# DisolvedOxygen.net
KiCad netlist of a schematic drawn in EAGLE
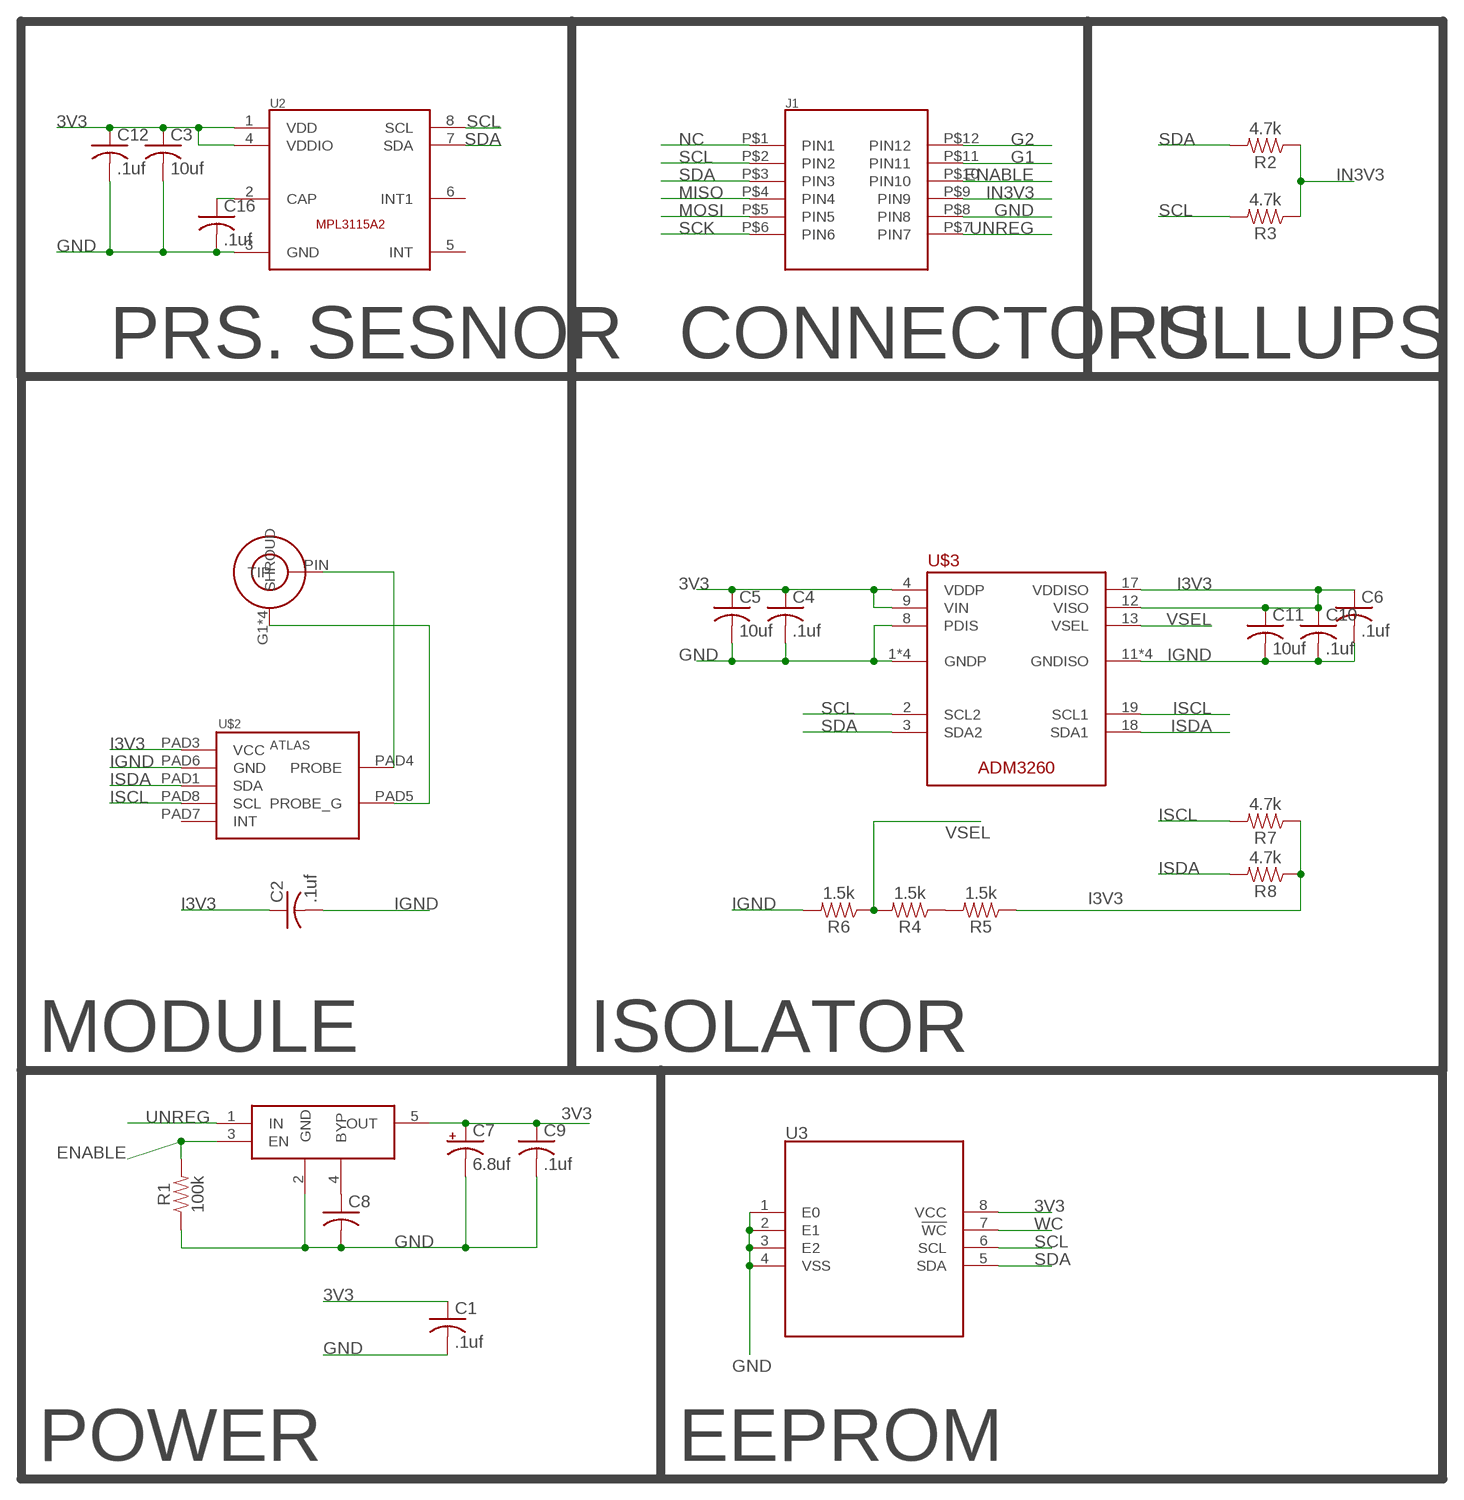
[diagram p0: schematic, sheet 1]

(export (version "E")
  (design (tool "Eeschema 10.0.6"))
  (components
    (comp (ref "C1")
      (value ".1uf")
      (footprint "eagle-import:C0603K")
      (libsource (lib "eagle-import") (part "C-USC0603K"))
    )
    (comp (ref "C2")
      (value ".1uf")
      (footprint "eagle-import:C0603K")
      (libsource (lib "eagle-import") (part "C-USC0603K"))
    )
    (comp (ref "C3")
      (value "10uf")
      (footprint "eagle-import:C0603K")
      (libsource (lib "eagle-import") (part "C-USC0603K"))
    )
    (comp (ref "C4")
      (value ".1uf")
      (footprint "eagle-import:C0603K")
      (libsource (lib "eagle-import") (part "C-USC0603K"))
    )
    (comp (ref "C5")
      (value "10uf")
      (footprint "eagle-import:C0603K")
      (libsource (lib "eagle-import") (part "C-USC0603K"))
    )
    (comp (ref "C6")
      (value ".1uf")
      (footprint "eagle-import:C0603K")
      (libsource (lib "eagle-import") (part "C-USC0603K"))
    )
    (comp (ref "C7")
      (value "6.8uf")
      (footprint "eagle-import:A_3216-18R")
      (libsource (lib "eagle-import") (part "CPOL-USA/3216-18R"))
    )
    (comp (ref "C8")
      (value "C-USC0603K")
      (footprint "eagle-import:C0603K")
      (libsource (lib "eagle-import") (part "C-USC0603K"))
    )
    (comp (ref "C9")
      (value ".1uf")
      (footprint "eagle-import:C0603K")
      (libsource (lib "eagle-import") (part "C-USC0603K"))
    )
    (comp (ref "C10")
      (value ".1uf")
      (footprint "eagle-import:C0603K")
      (libsource (lib "eagle-import") (part "C-USC0603K"))
    )
    (comp (ref "C11")
      (value "10uf")
      (footprint "eagle-import:C0603K")
      (libsource (lib "eagle-import") (part "C-USC0603K"))
    )
    (comp (ref "C12")
      (value ".1uf")
      (footprint "eagle-import:C0603K")
      (libsource (lib "eagle-import") (part "C-USC0603K"))
    )
    (comp (ref "C16")
      (value ".1uf")
      (footprint "eagle-import:C0603K")
      (libsource (lib "eagle-import") (part "C-USC0603K"))
    )
    (comp (ref "J1")
      (value "2X6-HEADERS")
      (footprint "eagle-import:M20-7810645")
      (libsource (lib "eagle-import") (part "2X6-HEADERS"))
    )
    (comp (ref "R1")
      (value "100k")
      (footprint "eagle-import:0603")
      (libsource (lib "eagle-import") (part "100KOHM-0603-1/10W-1%"))
    )
    (comp (ref "R2")
      (value "4.7k")
      (footprint "eagle-import:0603")
      (libsource (lib "eagle-import") (part "100KOHM-0603-1/10W-1%"))
    )
    (comp (ref "R3")
      (value "4.7k")
      (footprint "eagle-import:0603")
      (libsource (lib "eagle-import") (part "100KOHM-0603-1/10W-1%"))
    )
    (comp (ref "R4")
      (value "1.5k")
      (footprint "eagle-import:0603")
      (libsource (lib "eagle-import") (part "100KOHM-0603-1/10W-1%"))
    )
    (comp (ref "R5")
      (value "1.5k")
      (footprint "eagle-import:0603")
      (libsource (lib "eagle-import") (part "100KOHM-0603-1/10W-1%"))
    )
    (comp (ref "R6")
      (value "1.5k")
      (footprint "eagle-import:0603")
      (libsource (lib "eagle-import") (part "100KOHM-0603-1/10W-1%"))
    )
    (comp (ref "R7")
      (value "4.7k")
      (footprint "eagle-import:0603")
      (libsource (lib "eagle-import") (part "100KOHM-0603-1/10W-1%"))
    )
    (comp (ref "R8")
      (value "4.7k")
      (footprint "eagle-import:0603")
      (libsource (lib "eagle-import") (part "100KOHM-0603-1/10W-1%"))
    )
    (comp (ref "U$1")
      (value "5-1814832-1")
      (footprint "eagle-import:5-1814832-1")
      (libsource (lib "eagle-import") (part "5-1814832-1"))
    )
    (comp (ref "U$2")
      (value "ATLAS10P")
      (footprint "eagle-import:ATLAS-10P")
      (libsource (lib "eagle-import") (part "ATLAS10P"))
    )
    (comp (ref "U$3")
      (value "ADM3260")
      (footprint "eagle-import:SOP65P780X200-20")
      (libsource (lib "eagle-import") (part "ADM3260"))
    )
    (comp (ref "U$4")
      (value "MIC5219-3.3YM5-TR")
      (footprint "eagle-import:SOT95P280X145-5")
      (libsource (lib "eagle-import") (part "MIC5219-3.3YM5-TR"))
    )
    (comp (ref "U2")
      (value "MPL3115A2LGA8")
      (footprint "eagle-import:SON125P300X500X110-8")
      (libsource (lib "eagle-import") (part "MPL3115A2LGA8"))
    )
    (comp (ref "U3")
      (value "M24C02-WMN6TP")
      (footprint "eagle-import:SOIC127P600X175-8")
      (libsource (lib "eagle-import") (part "M24C02-WMN6TP"))
    )
  )
  (nets
    (net (code "1") (name "/3V3") (class "Default")
      (node (ref "C1") (pin "1") (pinfunction "1_1") (pintype "passive"))
      (node (ref "C12") (pin "1") (pinfunction "1_1") (pintype "passive"))
      (node (ref "C3") (pin "1") (pinfunction "1_1") (pintype "passive"))
      (node (ref "C4") (pin "1") (pinfunction "1_1") (pintype "passive"))
      (node (ref "C5") (pin "1") (pinfunction "1_1") (pintype "passive"))
      (node (ref "C7") (pin "+") (pinfunction "+_+") (pintype "passive"))
      (node (ref "C9") (pin "1") (pinfunction "1_1") (pintype "passive"))
      (node (ref "U$3") (pin "4") (pinfunction "VDDP_4") (pintype "bidirectional"))
      (node (ref "U$3") (pin "9") (pinfunction "VIN_9") (pintype "bidirectional"))
      (node (ref "U$4") (pin "5") (pinfunction "OUT_5") (pintype "bidirectional"))
      (node (ref "U2") (pin "1") (pinfunction "VDD_1") (pintype "bidirectional"))
      (node (ref "U2") (pin "4") (pinfunction "VDDIO_4") (pintype "bidirectional"))
      (node (ref "U3") (pin "8") (pinfunction "VCC_8") (pintype "bidirectional"))
    )
    (net (code "2") (name "/ENABLE") (class "Default")
      (node (ref "J1") (pin "P$10") (pinfunction "PIN10_P$10") (pintype "bidirectional"))
      (node (ref "R1") (pin "2") (pinfunction "2_2") (pintype "passive"))
      (node (ref "U$4") (pin "3") (pinfunction "EN_3") (pintype "bidirectional"))
    )
    (net (code "3") (name "/G1") (class "Default")
      (node (ref "J1") (pin "P$11") (pinfunction "PIN11_P$11") (pintype "bidirectional"))
    )
    (net (code "4") (name "/G2") (class "Default")
      (node (ref "J1") (pin "P$12") (pinfunction "PIN12_P$12") (pintype "bidirectional"))
    )
    (net (code "5") (name "/GND") (class "Default")
      (node (ref "C1") (pin "2") (pinfunction "2_2") (pintype "passive"))
      (node (ref "C12") (pin "2") (pinfunction "2_2") (pintype "passive"))
      (node (ref "C16") (pin "2") (pinfunction "2_2") (pintype "passive"))
      (node (ref "C3") (pin "2") (pinfunction "2_2") (pintype "passive"))
      (node (ref "C4") (pin "2") (pinfunction "2_2") (pintype "passive"))
      (node (ref "C5") (pin "2") (pinfunction "2_2") (pintype "passive"))
      (node (ref "C7") (pin "-") (pinfunction "-_-") (pintype "passive"))
      (node (ref "C8") (pin "2") (pinfunction "2_2") (pintype "passive"))
      (node (ref "C9") (pin "2") (pinfunction "2_2") (pintype "passive"))
      (node (ref "J1") (pin "P$8") (pinfunction "PIN8_P$8") (pintype "bidirectional"))
      (node (ref "R1") (pin "1") (pinfunction "1_1") (pintype "passive"))
      (node (ref "U$3") (pin "1") (pinfunction "GNDP_1") (pintype "bidirectional"))
      (node (ref "U$3") (pin "10") (pinfunction "GNDP_10") (pintype "bidirectional"))
      (node (ref "U$3") (pin "5") (pinfunction "GNDP_5") (pintype "bidirectional"))
      (node (ref "U$3") (pin "7") (pinfunction "GNDP_7") (pintype "bidirectional"))
      (node (ref "U$3") (pin "8") (pinfunction "PDIS_8") (pintype "bidirectional"))
      (node (ref "U$4") (pin "2") (pinfunction "GND_2") (pintype "bidirectional"))
      (node (ref "U2") (pin "3") (pinfunction "GND_3") (pintype "bidirectional"))
      (node (ref "U3") (pin "1") (pinfunction "E0_1") (pintype "bidirectional"))
      (node (ref "U3") (pin "2") (pinfunction "E1_2") (pintype "bidirectional"))
      (node (ref "U3") (pin "3") (pinfunction "E2_3") (pintype "bidirectional"))
      (node (ref "U3") (pin "4") (pinfunction "VSS_4") (pintype "bidirectional"))
    )
    (net (code "6") (name "/I3V3") (class "Default")
      (node (ref "C10") (pin "1") (pinfunction "1_1") (pintype "passive"))
      (node (ref "C11") (pin "1") (pinfunction "1_1") (pintype "passive"))
      (node (ref "C2") (pin "1") (pinfunction "1_1") (pintype "passive"))
      (node (ref "C6") (pin "1") (pinfunction "1_1") (pintype "passive"))
      (node (ref "R5") (pin "1") (pinfunction "1_1") (pintype "passive"))
      (node (ref "R7") (pin "1") (pinfunction "1_1") (pintype "passive"))
      (node (ref "R8") (pin "1") (pinfunction "1_1") (pintype "passive"))
      (node (ref "U$2") (pin "PAD3") (pinfunction "VCC_PAD3") (pintype "bidirectional"))
      (node (ref "U$3") (pin "12") (pinfunction "VISO_12") (pintype "bidirectional"))
      (node (ref "U$3") (pin "17") (pinfunction "VDDISO_17") (pintype "bidirectional"))
    )
    (net (code "7") (name "/IGND") (class "Default")
      (node (ref "C10") (pin "2") (pinfunction "2_2") (pintype "passive"))
      (node (ref "C11") (pin "2") (pinfunction "2_2") (pintype "passive"))
      (node (ref "C2") (pin "2") (pinfunction "2_2") (pintype "passive"))
      (node (ref "C6") (pin "2") (pinfunction "2_2") (pintype "passive"))
      (node (ref "R6") (pin "2") (pinfunction "2_2") (pintype "passive"))
      (node (ref "U$2") (pin "PAD6") (pinfunction "GND_PAD6") (pintype "bidirectional"))
      (node (ref "U$3") (pin "11") (pinfunction "GNDISO_11") (pintype "bidirectional"))
      (node (ref "U$3") (pin "14") (pinfunction "GNDISO_14") (pintype "bidirectional"))
      (node (ref "U$3") (pin "16") (pinfunction "GNDISO_16") (pintype "bidirectional"))
      (node (ref "U$3") (pin "20") (pinfunction "GNDISO_20") (pintype "bidirectional"))
    )
    (net (code "8") (name "/IN3V3") (class "Default")
      (node (ref "J1") (pin "P$9") (pinfunction "PIN9_P$9") (pintype "bidirectional"))
      (node (ref "R2") (pin "1") (pinfunction "1_1") (pintype "passive"))
      (node (ref "R3") (pin "1") (pinfunction "1_1") (pintype "passive"))
    )
    (net (code "9") (name "/ISCL") (class "Default")
      (node (ref "R7") (pin "2") (pinfunction "2_2") (pintype "passive"))
      (node (ref "U$2") (pin "PAD8") (pinfunction "SCL_PAD8") (pintype "bidirectional"))
      (node (ref "U$3") (pin "19") (pinfunction "SCL1_19") (pintype "bidirectional"))
    )
    (net (code "10") (name "/ISDA") (class "Default")
      (node (ref "R8") (pin "2") (pinfunction "2_2") (pintype "passive"))
      (node (ref "U$2") (pin "PAD1") (pinfunction "SDA_PAD1") (pintype "bidirectional"))
      (node (ref "U$3") (pin "18") (pinfunction "SDA1_18") (pintype "bidirectional"))
    )
    (net (code "11") (name "/MISO") (class "Default")
      (node (ref "J1") (pin "P$4") (pinfunction "PIN4_P$4") (pintype "bidirectional"))
    )
    (net (code "12") (name "/MOSI") (class "Default")
      (node (ref "J1") (pin "P$5") (pinfunction "PIN5_P$5") (pintype "bidirectional"))
    )
    (net (code "13") (name "/NC") (class "Default")
      (node (ref "J1") (pin "P$1") (pinfunction "PIN1_P$1") (pintype "bidirectional"))
    )
    (net (code "14") (name "/SCK") (class "Default")
      (node (ref "J1") (pin "P$6") (pinfunction "PIN6_P$6") (pintype "bidirectional"))
    )
    (net (code "15") (name "/SCL") (class "Default")
      (node (ref "J1") (pin "P$2") (pinfunction "PIN2_P$2") (pintype "bidirectional"))
      (node (ref "R3") (pin "2") (pinfunction "2_2") (pintype "passive"))
      (node (ref "U$3") (pin "2") (pinfunction "SCL2_2") (pintype "bidirectional"))
      (node (ref "U2") (pin "8") (pinfunction "SCL_8") (pintype "bidirectional"))
      (node (ref "U3") (pin "6") (pinfunction "SCL_6") (pintype "bidirectional"))
    )
    (net (code "16") (name "/SDA") (class "Default")
      (node (ref "J1") (pin "P$3") (pinfunction "PIN3_P$3") (pintype "bidirectional"))
      (node (ref "R2") (pin "2") (pinfunction "2_2") (pintype "passive"))
      (node (ref "U$3") (pin "3") (pinfunction "SDA2_3") (pintype "bidirectional"))
      (node (ref "U2") (pin "7") (pinfunction "SDA_7") (pintype "bidirectional"))
      (node (ref "U3") (pin "5") (pinfunction "SDA_5") (pintype "bidirectional"))
    )
    (net (code "17") (name "/UNREG") (class "Default")
      (node (ref "J1") (pin "P$7") (pinfunction "PIN7_P$7") (pintype "bidirectional"))
      (node (ref "U$4") (pin "1") (pinfunction "IN_1") (pintype "bidirectional"))
    )
    (net (code "18") (name "/VSEL") (class "Default")
      (node (ref "R4") (pin "2") (pinfunction "2_2") (pintype "passive"))
      (node (ref "R6") (pin "1") (pinfunction "1_1") (pintype "passive"))
      (node (ref "U$3") (pin "13") (pinfunction "VSEL_13") (pintype "bidirectional"))
    )
    (net (code "19") (name "/WC") (class "Default")
      (node (ref "U3") (pin "7") (pinfunction "~{WC}_7") (pintype "bidirectional"))
    )
    (net (code "20") (name "Net-(R4-Pad1)") (class "Default")
      (node (ref "R4") (pin "1") (pinfunction "1_1") (pintype "passive"))
      (node (ref "R5") (pin "2") (pinfunction "2_2") (pintype "passive"))
    )
    (net (code "21") (name "Net-(U$1-TIP)") (class "Default")
      (node (ref "U$1") (pin "PIN") (pinfunction "TIP_PIN") (pintype "bidirectional"))
      (node (ref "U$2") (pin "PAD4") (pinfunction "PROBE_PAD4") (pintype "bidirectional"))
    )
    (net (code "22") (name "Net-(U$2-PROBE_G)") (class "Default")
      (node (ref "U$1") (pin "G1") (pinfunction "SHROUD_G1") (pintype "bidirectional"))
      (node (ref "U$1") (pin "G2") (pinfunction "SHROUD_G2") (pintype "bidirectional"))
      (node (ref "U$1") (pin "G3") (pinfunction "SHROUD_G3") (pintype "bidirectional"))
      (node (ref "U$1") (pin "G4") (pinfunction "SHROUD_G4") (pintype "bidirectional"))
      (node (ref "U$2") (pin "PAD5") (pinfunction "PROBE_G_PAD5") (pintype "bidirectional"))
    )
    (net (code "23") (name "Net-(U$4-BYP)") (class "Default")
      (node (ref "C8") (pin "1") (pinfunction "1_1") (pintype "passive"))
      (node (ref "U$4") (pin "4") (pinfunction "BYP_4") (pintype "bidirectional"))
    )
    (net (code "24") (name "Net-(U2-CAP)") (class "Default")
      (node (ref "C16") (pin "1") (pinfunction "1_1") (pintype "passive"))
      (node (ref "U2") (pin "2") (pinfunction "CAP_2") (pintype "bidirectional"))
    )
    (net (code "25") (name "unconnected-(U$2-INT-PadPAD7)") (class "Default")
      (node (ref "U$2") (pin "PAD7") (pinfunction "INT_PAD7") (pintype "bidirectional"))
    )
    (net (code "26") (name "unconnected-(U2-INT-Pad5)") (class "Default")
      (node (ref "U2") (pin "5") (pinfunction "INT_5") (pintype "bidirectional"))
    )
    (net (code "27") (name "unconnected-(U2-INT1-Pad6)") (class "Default")
      (node (ref "U2") (pin "6") (pinfunction "INT1_6") (pintype "bidirectional"))
    )
  )
)
